# Tempature_Sensor.net
KiCad netlist of a schematic drawn in Altium Designer
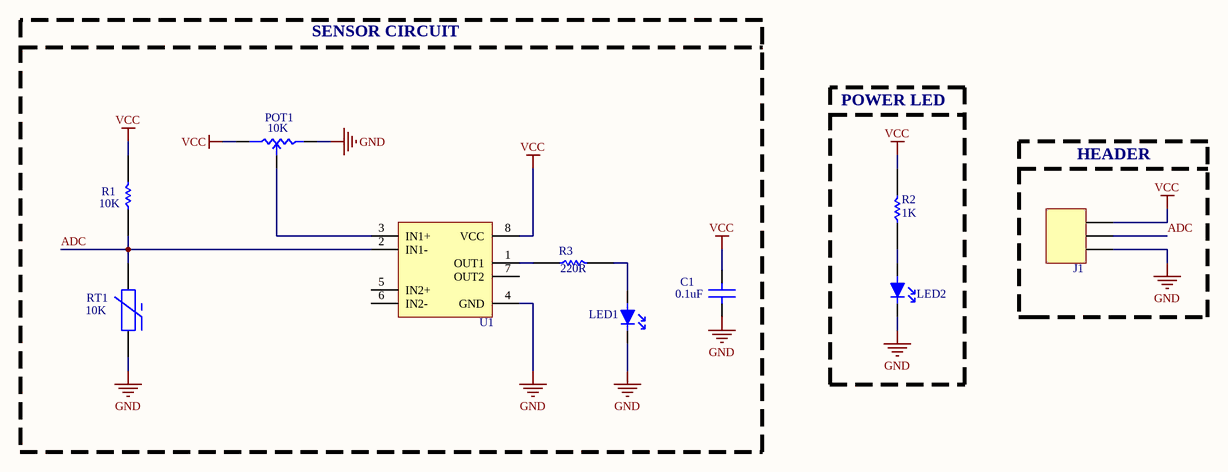
[diagram p0: Tempature Sensor.SchDoc]

(export (version "E")
  (design (tool "Eeschema 10.0.6"))
  (components
    (comp (ref "C1")
      (value "0.1uF")
      (footprint "CAP_0805")
      (description "CAP CER 0.1UF 50V X7R 0805")
      (fields (field (name "Comment") "CC0805KRX7R9BB104"))
      (libsource (lib "Tempature Sensor") (part "CAP CER 0.1UF"))
    )
    (comp (ref "J1")
      (value "61300311121")
      (footprint "HEADER")
      (description "CONN HEADER 3POS 2.54MM")
      (libsource (lib "Tempature Sensor") (part "HEADER"))
    )
    (comp (ref "LED1")
      (value "150080RS75000")
      (footprint "LED_0805")
      (description "LED RED 0805 SMD")
      (libsource (lib "Tempature Sensor") (part "LED SMD"))
    )
    (comp (ref "LED2")
      (value "150080RS75000")
      (footprint "LED_0805")
      (description "LED RED 0805 SMD")
      (libsource (lib "Tempature Sensor") (part "LED SMD"))
    )
    (comp (ref "POT1")
      (value "10K")
      (footprint "TRIMMER")
      (description "TRIMMER 10K OHM 0.5W")
      (fields (field (name "Comment") "PV36W103C01B00"))
      (libsource (lib "Tempature Sensor") (part "POT 10K"))
    )
    (comp (ref "R1")
      (value "10K")
      (footprint "RES_0805")
      (description "RES 10K OHM 5% 1/8W 0805")
      (fields (field (name "Comment") "RC0805JR-0710KL"))
      (libsource (lib "Tempature Sensor") (part "RES 10K OHM"))
    )
    (comp (ref "R2")
      (value "1K")
      (footprint "RES_0805")
      (description "RES 1K OHM 5% 1/8W 0805")
      (fields (field (name "Comment") "RC0805JR-071KL"))
      (libsource (lib "Tempature Sensor") (part "RES 1K OHM"))
    )
    (comp (ref "R3")
      (value "220R")
      (footprint "RES_0805")
      (description "RES 220 OHM 5% 1/8W 0805")
      (fields (field (name "Comment") "RC0805JR-07220RL"))
      (libsource (lib "Tempature Sensor") (part "RES 220 OHM"))
    )
    (comp (ref "RT1")
      (value "10K")
      (footprint "NTC")
      (description "THERMISTOR NTC 10KOHM 4300K")
      (fields (field (name "Comment") "B57164K0103J000"))
      (libsource (lib "Tempature Sensor") (part "NTC"))
    )
    (comp (ref "U1")
      (value "LM358S-13")
      (footprint "SO-8")
      (description "IC OPAMP GP 2 CIRCUIT 8SO")
      (libsource (lib "Tempature Sensor") (part "OPAMP"))
    )
  )
  (nets
    (net (code "1") (name "/ADC") (class "Default")
      (node (ref "J1") (pin "2") (pintype "passive"))
      (node (ref "R1") (pin "1") (pintype "passive"))
      (node (ref "RT1") (pin "2") (pintype "passive"))
      (node (ref "U1") (pin "2") (pinfunction "IN1-_2") (pintype "passive"))
    )
    (net (code "2") (name "GND") (class "Default")
      (node (ref "C1") (pin "1") (pintype "passive"))
      (node (ref "J1") (pin "1") (pintype "passive"))
      (node (ref "LED1") (pin "2") (pintype "passive"))
      (node (ref "LED2") (pin "2") (pintype "passive"))
      (node (ref "POT1") (pin "1") (pintype "passive"))
      (node (ref "RT1") (pin "1") (pintype "passive"))
      (node (ref "U1") (pin "4") (pinfunction "GND_4") (pintype "passive"))
    )
    (net (code "3") (name "Net-(LED1-Pad1)") (class "Default")
      (node (ref "LED1") (pin "1") (pintype "passive"))
      (node (ref "R3") (pin "2") (pintype "passive"))
    )
    (net (code "4") (name "Net-(LED2-Pad1)") (class "Default")
      (node (ref "LED2") (pin "1") (pintype "passive"))
      (node (ref "R2") (pin "1") (pintype "passive"))
    )
    (net (code "5") (name "Net-(U1-IN1+)") (class "Default")
      (node (ref "POT1") (pin "2") (pintype "passive"))
      (node (ref "U1") (pin "3") (pinfunction "IN1+_3") (pintype "passive"))
    )
    (net (code "6") (name "Net-(U1-OUT1)") (class "Default")
      (node (ref "R3") (pin "1") (pintype "passive"))
      (node (ref "U1") (pin "1") (pinfunction "OUT1_1") (pintype "passive"))
    )
    (net (code "7") (name "VCC") (class "Default")
      (node (ref "C1") (pin "2") (pintype "passive"))
      (node (ref "J1") (pin "3") (pintype "passive"))
      (node (ref "POT1") (pin "3") (pintype "passive"))
      (node (ref "R1") (pin "2") (pintype "passive"))
      (node (ref "R2") (pin "2") (pintype "passive"))
      (node (ref "U1") (pin "8") (pinfunction "VCC_8") (pintype "passive"))
    )
    (net (code "8") (name "unconnected-(U1-IN2+-Pad5)") (class "Default")
      (node (ref "U1") (pin "5") (pinfunction "IN2+_5") (pintype "passive"))
    )
    (net (code "9") (name "unconnected-(U1-IN2--Pad6)") (class "Default")
      (node (ref "U1") (pin "6") (pinfunction "IN2-_6") (pintype "passive"))
    )
    (net (code "10") (name "unconnected-(U1-OUT2-Pad7)") (class "Default")
      (node (ref "U1") (pin "7") (pinfunction "OUT2_7") (pintype "passive"))
    )
  )
)
